# Sheet2.net
KiCad netlist of a schematic drawn in Altium Designer
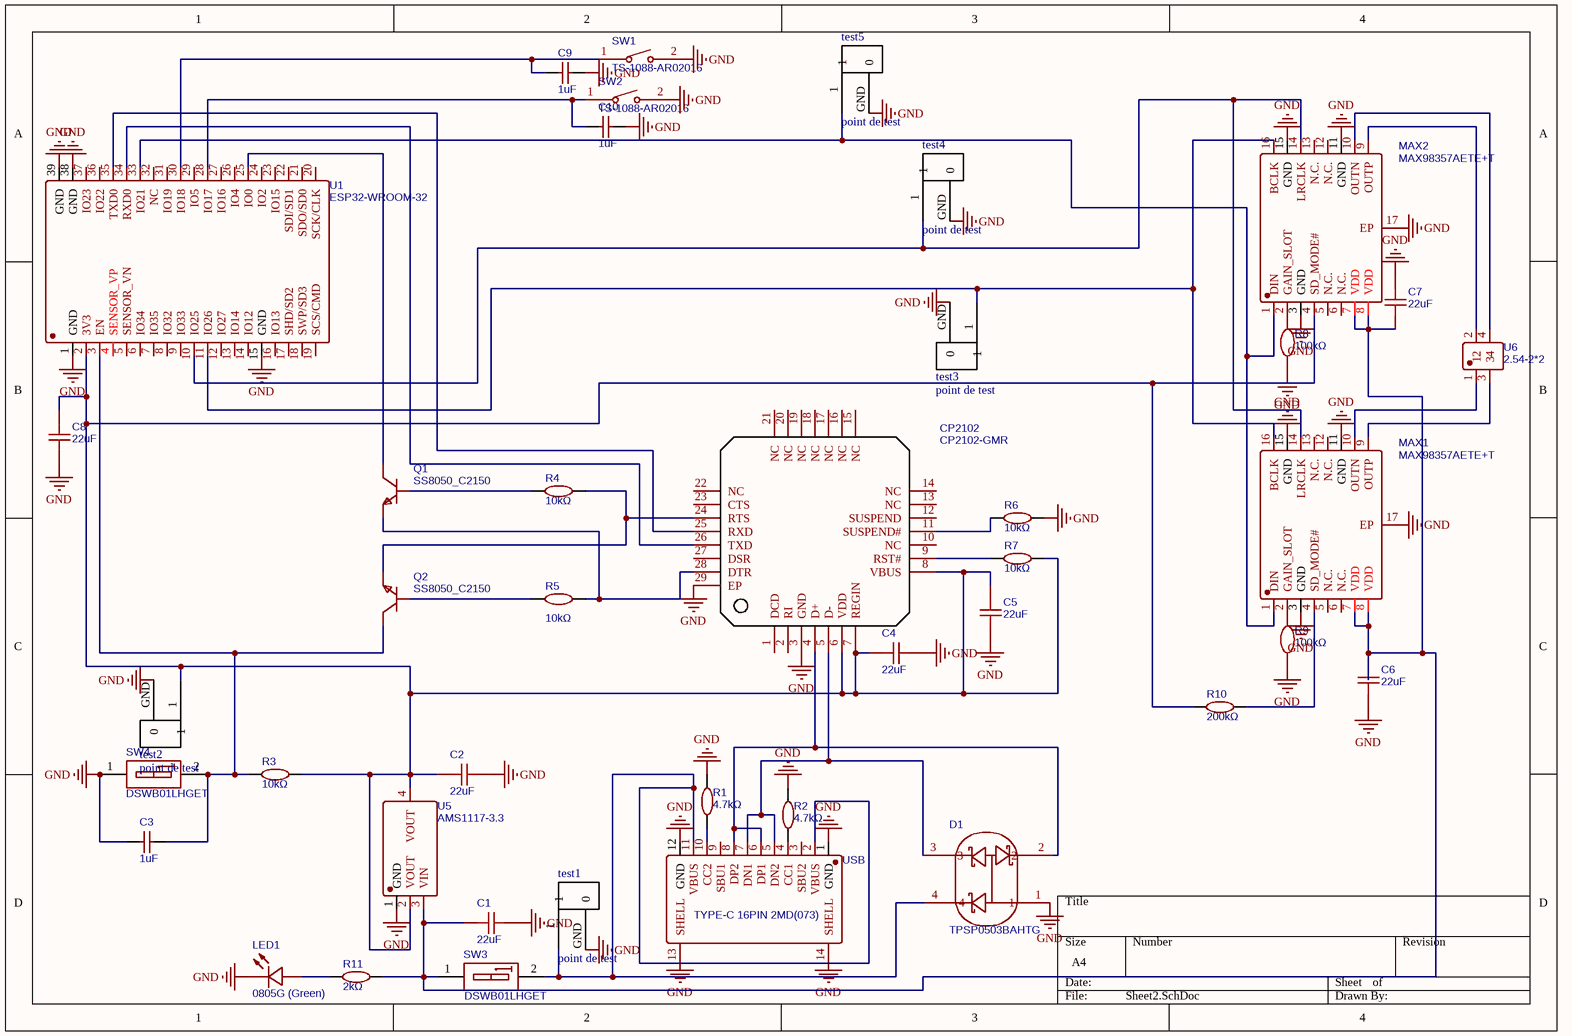
[diagram p0: Sheet2.SchDoc]

(export (version "E")
  (design (tool "Eeschema 10.0.6"))
  (components
    (comp (ref "C1")
      (value "22uF")
      (footprint "C0805")
      (fields
        (field (name "MANUFACTURER") "SAMSUNG(三星)")
        (field (name "MANUFACTURER PART") "CL21A226MAQNNNE")
      )
      (libsource (lib "LIBRAIRIE PROJET") (part "22uF"))
    )
    (comp (ref "C2")
      (value "22uF")
      (footprint "C0805")
      (fields
        (field (name "MANUFACTURER") "SAMSUNG(三星)")
        (field (name "MANUFACTURER PART") "CL21A226MAQNNNE")
      )
      (libsource (lib "LIBRAIRIE PROJET") (part "22uF"))
    )
    (comp (ref "C3")
      (value "1uF")
      (footprint "C0805")
      (fields
        (field (name "MANUFACTURER PART") "CL21B105KBFNNNE")
        (field (name "MANUFACTURER") "SAMSUNG(三星)")
      )
      (libsource (lib "LIBRAIRIE PROJET") (part "1uF"))
    )
    (comp (ref "C4")
      (value "22uF")
      (footprint "C0805")
      (fields
        (field (name "MANUFACTURER") "SAMSUNG(三星)")
        (field (name "MANUFACTURER PART") "CL21A226MAQNNNE")
      )
      (libsource (lib "LIBRAIRIE PROJET") (part "22uF"))
    )
    (comp (ref "C5")
      (value "22uF")
      (footprint "C0805")
      (fields
        (field (name "MANUFACTURER") "SAMSUNG(三星)")
        (field (name "MANUFACTURER PART") "CL21A226MAQNNNE")
      )
      (libsource (lib "LIBRAIRIE PROJET") (part "22uF"))
    )
    (comp (ref "C6")
      (value "22uF")
      (footprint "C0805")
      (fields
        (field (name "MANUFACTURER") "SAMSUNG(三星)")
        (field (name "MANUFACTURER PART") "CL21A226MAQNNNE")
      )
      (libsource (lib "LIBRAIRIE PROJET") (part "22uF"))
    )
    (comp (ref "C7")
      (value "22uF")
      (footprint "C0805")
      (fields
        (field (name "MANUFACTURER") "SAMSUNG(三星)")
        (field (name "MANUFACTURER PART") "CL21A226MAQNNNE")
      )
      (libsource (lib "LIBRAIRIE PROJET") (part "22uF"))
    )
    (comp (ref "C8")
      (value "22uF")
      (footprint "C0805")
      (fields
        (field (name "MANUFACTURER") "SAMSUNG(三星)")
        (field (name "MANUFACTURER PART") "CL21A226MAQNNNE")
      )
      (libsource (lib "LIBRAIRIE PROJET") (part "22uF"))
    )
    (comp (ref "C9")
      (value "1uF")
      (footprint "C0805")
      (fields
        (field (name "MANUFACTURER PART") "CL21B105KBFNNNE")
        (field (name "MANUFACTURER") "SAMSUNG(三星)")
      )
      (libsource (lib "LIBRAIRIE PROJET") (part "1uF"))
    )
    (comp (ref "C10")
      (value "1uF")
      (footprint "C0805")
      (fields
        (field (name "MANUFACTURER PART") "CL21B105KBFNNNE")
        (field (name "MANUFACTURER") "SAMSUNG(三星)")
      )
      (libsource (lib "LIBRAIRIE PROJET") (part "1uF"))
    )
    (comp (ref "CP2102")
      (value "CP2102-GMR")
      (footprint "WQFN-28_L5.0-W5.0-P0.50-BL-EP3.2")
      (fields (field (name "MANUFACTURER") "SKYWORKS/SILICON LABS(芯科)"))
      (libsource (lib "LIBRAIRIE PROJET") (part "CP2102-GMR"))
    )
    (comp (ref "D1")
      (value "TPSP0503BAHTG")
      (footprint "SOT-143-4_L2.9-W1.3-P1.92-LS2.4-BL")
      (fields (field (name "MANUFACTURER") "TECH PUBLIC(台舟)") (field (name "CONTRIBUTOR") "LCSC"))
      (libsource (lib "LIBRAIRIE PROJET") (part "TPSP0503BAHTG"))
    )
    (comp (ref "LED1")
      (value "0805G (Green)")
      (footprint "LED0805-R-RD")
      (fields (field (name "MANUFACTURER") "KENTO") (field (name "MANUFACTURER PART") "KT-0805翠绿"))
      (libsource (lib "LIBRAIRIE PROJET") (part "0805G (Green)"))
    )
    (comp (ref "MAX1")
      (value "MAX98357AETE+T")
      (footprint "TQFN-16_L3.0-W3.0-P0.50-BL-EP1.5")
      (fields (field (name "MANUFACTURER") "ADI(亚德诺)/MAXIM(美信)") (field (name "CONTRIBUTOR") "LCSC"))
      (libsource (lib "LIBRAIRIE PROJET") (part "MAX98357AETE+T"))
    )
    (comp (ref "MAX2")
      (value "MAX98357AETE+T")
      (footprint "TQFN-16_L3.0-W3.0-P0.50-BL-EP1.5")
      (fields (field (name "MANUFACTURER") "ADI(亚德诺)/MAXIM(美信)") (field (name "CONTRIBUTOR") "LCSC"))
      (libsource (lib "LIBRAIRIE PROJET") (part "MAX98357AETE+T"))
    )
    (comp (ref "Q1")
      (value "SS8050_C2150")
      (footprint "SOT-23-3_L2.9-W1.3-P1.90-LS2.4-BR")
      (fields (field (name "MANUFACTURER") "CJ(江苏长电/长晶)") (field (name "MANUFACTURER PART") "SS8050"))
      (libsource (lib "LIBRAIRIE PROJET") (part "SS8050_C2150"))
    )
    (comp (ref "Q2")
      (value "SS8050_C2150")
      (footprint "SOT-23-3_L2.9-W1.3-P1.90-LS2.4-BR")
      (fields (field (name "MANUFACTURER") "CJ(江苏长电/长晶)") (field (name "MANUFACTURER PART") "SS8050"))
      (libsource (lib "LIBRAIRIE PROJET") (part "SS8050_C2150"))
    )
    (comp (ref "R1")
      (value "4.7kΩ")
      (footprint "R0805")
      (fields
        (field (name "MANUFACTURER") "UNI-ROYAL(厚声)")
        (field (name "MANUFACTURER PART") "0805W8F4701T5E")
      )
      (libsource (lib "LIBRAIRIE PROJET") (part "4.7kΩ"))
    )
    (comp (ref "R2")
      (value "4.7kΩ")
      (footprint "R0805")
      (fields
        (field (name "MANUFACTURER") "UNI-ROYAL(厚声)")
        (field (name "MANUFACTURER PART") "0805W8F4701T5E")
      )
      (libsource (lib "LIBRAIRIE PROJET") (part "4.7kΩ"))
    )
    (comp (ref "R3")
      (value "10kΩ")
      (footprint "R0805")
      (fields
        (field (name "MANUFACTURER") "UNI-ROYAL(厚声)")
        (field (name "MANUFACTURER PART") "0805W8F1002T5E")
      )
      (libsource (lib "LIBRAIRIE PROJET") (part "10kΩ"))
    )
    (comp (ref "R4")
      (value "10kΩ")
      (footprint "R0805")
      (fields
        (field (name "MANUFACTURER") "UNI-ROYAL(厚声)")
        (field (name "MANUFACTURER PART") "0805W8F1002T5E")
      )
      (libsource (lib "LIBRAIRIE PROJET") (part "10kΩ"))
    )
    (comp (ref "R5")
      (value "10kΩ")
      (footprint "R0805")
      (fields
        (field (name "MANUFACTURER") "UNI-ROYAL(厚声)")
        (field (name "MANUFACTURER PART") "0805W8F1002T5E")
      )
      (libsource (lib "LIBRAIRIE PROJET") (part "10kΩ"))
    )
    (comp (ref "R6")
      (value "10kΩ")
      (footprint "R0805")
      (fields
        (field (name "MANUFACTURER") "UNI-ROYAL(厚声)")
        (field (name "MANUFACTURER PART") "0805W8F1002T5E")
      )
      (libsource (lib "LIBRAIRIE PROJET") (part "10kΩ"))
    )
    (comp (ref "R7")
      (value "10kΩ")
      (footprint "R0805")
      (fields
        (field (name "MANUFACTURER") "UNI-ROYAL(厚声)")
        (field (name "MANUFACTURER PART") "0805W8F1002T5E")
      )
      (libsource (lib "LIBRAIRIE PROJET") (part "10kΩ"))
    )
    (comp (ref "R8")
      (value "100kΩ")
      (footprint "R0805")
      (fields
        (field (name "MANUFACTURER") "FOJAN(富捷)")
        (field (name "MANUFACTURER PART") "FRC0805J104 TS")
        (field (name "CONTRIBUTOR") "lcsc")
      )
      (libsource (lib "LIBRAIRIE PROJET") (part "100kΩ"))
    )
    (comp (ref "R9")
      (value "100kΩ")
      (footprint "R0805")
      (fields
        (field (name "MANUFACTURER") "FOJAN(富捷)")
        (field (name "MANUFACTURER PART") "FRC0805J104 TS")
        (field (name "CONTRIBUTOR") "lcsc")
      )
      (libsource (lib "LIBRAIRIE PROJET") (part "100kΩ"))
    )
    (comp (ref "R10")
      (value "200kΩ")
      (footprint "R0805")
      (fields
        (field (name "MANUFACTURER") "UNI-ROYAL(厚声)")
        (field (name "MANUFACTURER PART") "0805W8F2003T5E")
      )
      (libsource (lib "LIBRAIRIE PROJET") (part "200kΩ"))
    )
    (comp (ref "R11")
      (value "2kΩ")
      (footprint "R0805")
      (fields
        (field (name "MANUFACTURER") "UNI-ROYAL(厚声)")
        (field (name "MANUFACTURER PART") "0805W8F2001T5E")
      )
      (libsource (lib "LIBRAIRIE PROJET") (part "2kΩ"))
    )
    (comp (ref "SW1")
      (value "TS-1088-AR02016")
      (footprint "SW-SMD_L3.9-W3.0-P4.45")
      (fields (field (name "MANUFACTURER") "XUNPU(讯普)") (field (name "CONTRIBUTOR") "LCSC"))
      (libsource (lib "LIBRAIRIE PROJET") (part "TS-1088-AR02016"))
    )
    (comp (ref "SW2")
      (value "TS-1088-AR02016")
      (footprint "SW-SMD_L3.9-W3.0-P4.45")
      (fields (field (name "MANUFACTURER") "XUNPU(讯普)") (field (name "CONTRIBUTOR") "LCSC"))
      (libsource (lib "LIBRAIRIE PROJET") (part "TS-1088-AR02016"))
    )
    (comp (ref "SW3")
      (value "DSWB01LHGET")
      (footprint "SW-TH_DSWB01LHGET")
      (fields (field (name "MANUFACTURER") "YE"))
      (libsource (lib "LIBRAIRIE PROJET") (part "DSWB01LHGET"))
    )
    (comp (ref "SW4")
      (value "DSWB01LHGET")
      (footprint "SW-TH_DSWB01LHGET")
      (fields (field (name "MANUFACTURER") "YE"))
      (libsource (lib "LIBRAIRIE PROJET") (part "DSWB01LHGET"))
    )
    (comp (ref "test1")
      (value "point de test")
      (footprint "LIBRAIRIE PCB:point de test")
      (libsource (lib "LIBRAIRIE PROJET") (part "point de test"))
    )
    (comp (ref "test2")
      (value "point de test")
      (footprint "LIBRAIRIE PCB:point de test")
      (libsource (lib "LIBRAIRIE PROJET") (part "point de test"))
    )
    (comp (ref "test3")
      (value "point de test")
      (footprint "LIBRAIRIE PCB:point de test")
      (libsource (lib "LIBRAIRIE PROJET") (part "point de test"))
    )
    (comp (ref "test4")
      (value "point de test")
      (footprint "LIBRAIRIE PCB:point de test")
      (libsource (lib "LIBRAIRIE PROJET") (part "point de test"))
    )
    (comp (ref "test5")
      (value "point de test")
      (footprint "LIBRAIRIE PCB:point de test")
      (libsource (lib "LIBRAIRIE PROJET") (part "point de test"))
    )
    (comp (ref "U1")
      (value "ESP32-WROOM-32")
      (footprint "WIFIM-SMD_ESP32-WROOM-32-N4")
      (fields
        (field (name "MANUFACTURER") "ESPRESSIF(乐鑫)")
        (field (name "MANUFACTURER PART") "ESP32-WROOM-32-N4")
        (field (name "CONTRIBUTOR") "LCSC")
      )
      (libsource (lib "LIBRAIRIE PROJET") (part "ESP32-WROOM-32"))
    )
    (comp (ref "U5")
      (value "AMS1117-3.3")
      (footprint "SOT-223-3_L6.5-W3.4-P2.30-LS7.0-BR")
      (fields (field (name "MANUFACTURER") "AMS"))
      (libsource (lib "LIBRAIRIE PROJET") (part "AMS1117-3.3"))
    )
    (comp (ref "U6")
      (value "2.54-2*2")
      (footprint "HDR-TH_4P-P2.54-V-F-R2-C2-S2.54")
      (fields (field (name "MANUFACTURER") "ZHOURI(洲日)") (field (name "CONTRIBUTOR") "LCSC"))
      (libsource (lib "LIBRAIRIE PROJET") (part "2.54-2*2"))
    )
    (comp (ref "USB")
      (value "TYPE-C 16PIN 2MD(073)")
      (footprint "USB-C-SMD_TYPE-C-6PIN-2MD-073")
      (fields (field (name "MANUFACTURER") "SHOU HAN(首韩)") (field (name "CONTRIBUTOR") "LCSC"))
      (libsource (lib "LIBRAIRIE PROJET") (part "TYPE-C 16PIN 2MD(073)"))
    )
  )
  (nets
    (net (code "1") (name "GND") (class "Default")
      (node (ref "C1") (pin "2") (pinfunction "2_2") (pintype "passive"))
      (node (ref "C10") (pin "2") (pinfunction "2_2") (pintype "passive"))
      (node (ref "C2") (pin "2") (pinfunction "2_2") (pintype "passive"))
      (node (ref "C3") (pin "1") (pinfunction "1_1") (pintype "passive"))
      (node (ref "C4") (pin "2") (pinfunction "2_2") (pintype "passive"))
      (node (ref "C5") (pin "1") (pinfunction "1_1") (pintype "passive"))
      (node (ref "C6") (pin "1") (pinfunction "1_1") (pintype "passive"))
      (node (ref "C7") (pin "2") (pinfunction "2_2") (pintype "passive"))
      (node (ref "C8") (pin "2") (pinfunction "2_2") (pintype "passive"))
      (node (ref "C9") (pin "2") (pinfunction "2_2") (pintype "passive"))
      (node (ref "CP2102") (pin "29") (pinfunction "EP_29") (pintype "passive"))
      (node (ref "CP2102") (pin "3") (pinfunction "GND_3") (pintype "passive"))
      (node (ref "D1") (pin "1") (pinfunction "1_1") (pintype "passive"))
      (node (ref "LED1") (pin "2") (pinfunction "K_2") (pintype "passive"))
      (node (ref "MAX1") (pin "11") (pinfunction "GND_11") (pintype "passive"))
      (node (ref "MAX1") (pin "15") (pinfunction "GND_15") (pintype "passive"))
      (node (ref "MAX1") (pin "17") (pinfunction "EP_17") (pintype "passive"))
      (node (ref "MAX1") (pin "3") (pinfunction "GND_3") (pintype "passive"))
      (node (ref "MAX2") (pin "11") (pinfunction "GND_11") (pintype "passive"))
      (node (ref "MAX2") (pin "15") (pinfunction "GND_15") (pintype "passive"))
      (node (ref "MAX2") (pin "17") (pinfunction "EP_17") (pintype "passive"))
      (node (ref "MAX2") (pin "3") (pinfunction "GND_3") (pintype "passive"))
      (node (ref "R1") (pin "2") (pinfunction "2_2") (pintype "passive"))
      (node (ref "R2") (pin "2") (pinfunction "2_2") (pintype "passive"))
      (node (ref "R6") (pin "2") (pinfunction "2_2") (pintype "passive"))
      (node (ref "R8") (pin "1") (pinfunction "1_1") (pintype "passive"))
      (node (ref "R9") (pin "1") (pinfunction "1_1") (pintype "passive"))
      (node (ref "SW1") (pin "2") (pinfunction "2_2") (pintype "passive"))
      (node (ref "SW2") (pin "2") (pinfunction "2_2") (pintype "passive"))
      (node (ref "SW4") (pin "1") (pinfunction "A1_1") (pintype "passive"))
      (node (ref "U1") (pin "1") (pinfunction "GND_1") (pintype "passive"))
      (node (ref "U1") (pin "15") (pinfunction "GND_15") (pintype "passive"))
      (node (ref "U1") (pin "38") (pinfunction "GND_38") (pintype "passive"))
      (node (ref "U1") (pin "39") (pinfunction "GND_39") (pintype "passive"))
      (node (ref "U5") (pin "1") (pinfunction "GND_1") (pintype "passive"))
      (node (ref "USB") (pin "1") (pinfunction "GND_1") (pintype "passive"))
      (node (ref "USB") (pin "12") (pinfunction "GND_12") (pintype "passive"))
      (node (ref "USB") (pin "13") (pinfunction "SHELL_13") (pintype "passive"))
      (node (ref "USB") (pin "14") (pinfunction "SHELL_14") (pintype "passive"))
      (node (ref "test1") (pin "GND") (pinfunction "0_GND") (pintype "passive"))
      (node (ref "test2") (pin "GND") (pinfunction "0_GND") (pintype "passive"))
      (node (ref "test3") (pin "GND") (pinfunction "0_GND") (pintype "passive"))
      (node (ref "test4") (pin "GND") (pinfunction "0_GND") (pintype "passive"))
      (node (ref "test5") (pin "GND") (pinfunction "0_GND") (pintype "passive"))
    )
    (net (code "2") (name "Net-(CP2102-D+)") (class "Default")
      (node (ref "CP2102") (pin "4") (pinfunction "D+_4") (pintype "passive"))
      (node (ref "D1") (pin "2") (pinfunction "2_2") (pintype "passive"))
      (node (ref "USB") (pin "6") (pinfunction "DP1_6") (pintype "passive"))
      (node (ref "USB") (pin "8") (pinfunction "DP2_8") (pintype "passive"))
    )
    (net (code "3") (name "Net-(CP2102-D-)") (class "Default")
      (node (ref "CP2102") (pin "5") (pinfunction "D-_5") (pintype "passive"))
      (node (ref "D1") (pin "3") (pinfunction "3_3") (pintype "passive"))
      (node (ref "USB") (pin "5") (pinfunction "DN2_5") (pintype "passive"))
      (node (ref "USB") (pin "7") (pinfunction "DN1_7") (pintype "passive"))
    )
    (net (code "4") (name "Net-(CP2102-DTR)") (class "Default")
      (node (ref "CP2102") (pin "28") (pinfunction "DTR_28") (pintype "passive"))
      (node (ref "Q1") (pin "2") (pinfunction "E_2") (pintype "passive"))
      (node (ref "R5") (pin "2") (pinfunction "2_2") (pintype "passive"))
    )
    (net (code "5") (name "Net-(CP2102-REGIN)") (class "Default")
      (node (ref "C2") (pin "1") (pinfunction "1_1") (pintype "passive"))
      (node (ref "C4") (pin "1") (pinfunction "1_1") (pintype "passive"))
      (node (ref "C5") (pin "2") (pinfunction "2_2") (pintype "passive"))
      (node (ref "C8") (pin "1") (pinfunction "1_1") (pintype "passive"))
      (node (ref "CP2102") (pin "6") (pinfunction "VDD_6") (pintype "passive"))
      (node (ref "CP2102") (pin "7") (pinfunction "REGIN_7") (pintype "passive"))
      (node (ref "CP2102") (pin "8") (pinfunction "VBUS_8") (pintype "passive"))
      (node (ref "MAX2") (pin "4") (pinfunction "SD_MODE#_4") (pintype "passive"))
      (node (ref "R10") (pin "1") (pinfunction "1_1") (pintype "passive"))
      (node (ref "R3") (pin "2") (pinfunction "2_2") (pintype "passive"))
      (node (ref "R7") (pin "2") (pinfunction "2_2") (pintype "passive"))
      (node (ref "U1") (pin "2") (pinfunction "3V3_2") (pintype "passive"))
      (node (ref "U5") (pin "2") (pinfunction "VOUT_2") (pintype "passive"))
      (node (ref "U5") (pin "4") (pinfunction "VOUT_4") (pintype "passive"))
      (node (ref "test2") (pin "1") (pinfunction "1_1") (pintype "passive"))
    )
    (net (code "6") (name "Net-(CP2102-RST#)") (class "Default")
      (node (ref "CP2102") (pin "9") (pinfunction "RST#_9") (pintype "passive"))
      (node (ref "R7") (pin "1") (pinfunction "1_1") (pintype "passive"))
    )
    (net (code "7") (name "Net-(CP2102-RTS)") (class "Default")
      (node (ref "CP2102") (pin "24") (pinfunction "RTS_24") (pintype "passive"))
      (node (ref "Q2") (pin "2") (pinfunction "E_2") (pintype "passive"))
      (node (ref "R4") (pin "2") (pinfunction "2_2") (pintype "passive"))
    )
    (net (code "8") (name "Net-(CP2102-RXD)") (class "Default")
      (node (ref "CP2102") (pin "25") (pinfunction "RXD_25") (pintype "passive"))
      (node (ref "U1") (pin "35") (pinfunction "TXD0_35") (pintype "passive"))
    )
    (net (code "9") (name "Net-(CP2102-SUSPEND#)") (class "Default")
      (node (ref "CP2102") (pin "11") (pinfunction "SUSPEND#_11") (pintype "passive"))
      (node (ref "R6") (pin "1") (pinfunction "1_1") (pintype "passive"))
    )
    (net (code "10") (name "Net-(CP2102-TXD)") (class "Default")
      (node (ref "CP2102") (pin "26") (pinfunction "TXD_26") (pintype "passive"))
      (node (ref "U1") (pin "34") (pinfunction "RXD0_34") (pintype "passive"))
    )
    (net (code "11") (name "Net-(D1-Pad4)") (class "Default")
      (node (ref "D1") (pin "4") (pinfunction "4_4") (pintype "passive"))
      (node (ref "SW3") (pin "2") (pinfunction "2_2") (pintype "passive"))
      (node (ref "USB") (pin "11") (pinfunction "VBUS_11") (pintype "passive"))
      (node (ref "USB") (pin "2") (pinfunction "VBUS_2") (pintype "passive"))
      (node (ref "test1") (pin "1") (pinfunction "1_1") (pintype "passive"))
    )
    (net (code "12") (name "Net-(LED1-A)") (class "Default")
      (node (ref "LED1") (pin "1") (pinfunction "A_1") (pintype "passive"))
      (node (ref "R11") (pin "1") (pinfunction "1_1") (pintype "passive"))
    )
    (net (code "13") (name "Net-(MAX1-BCLK)") (class "Default")
      (node (ref "MAX1") (pin "16") (pinfunction "BCLK_16") (pintype "passive"))
      (node (ref "MAX2") (pin "16") (pinfunction "BCLK_16") (pintype "passive"))
      (node (ref "U1") (pin "11") (pinfunction "IO26_11") (pintype "passive"))
      (node (ref "test3") (pin "1") (pinfunction "1_1") (pintype "passive"))
    )
    (net (code "14") (name "Net-(MAX1-DIN)") (class "Default")
      (node (ref "MAX1") (pin "1") (pinfunction "DIN_1") (pintype "passive"))
      (node (ref "MAX2") (pin "1") (pinfunction "DIN_1") (pintype "passive"))
      (node (ref "U1") (pin "33") (pinfunction "IO21_33") (pintype "passive"))
      (node (ref "test5") (pin "1") (pinfunction "1_1") (pintype "passive"))
    )
    (net (code "15") (name "Net-(MAX1-GAIN_SLOT)") (class "Default")
      (node (ref "MAX1") (pin "2") (pinfunction "GAIN_SLOT_2") (pintype "passive"))
      (node (ref "R9") (pin "2") (pinfunction "2_2") (pintype "passive"))
    )
    (net (code "16") (name "Net-(MAX1-LRCLK)") (class "Default")
      (node (ref "MAX1") (pin "14") (pinfunction "LRCLK_14") (pintype "passive"))
      (node (ref "MAX2") (pin "14") (pinfunction "LRCLK_14") (pintype "passive"))
      (node (ref "U1") (pin "10") (pinfunction "IO25_10") (pintype "passive"))
      (node (ref "test4") (pin "1") (pinfunction "1_1") (pintype "passive"))
    )
    (net (code "17") (name "Net-(MAX1-OUTN)") (class "Default")
      (node (ref "MAX1") (pin "10") (pinfunction "OUTN_10") (pintype "passive"))
      (node (ref "U6") (pin "1") (pinfunction "1_1") (pintype "passive"))
    )
    (net (code "18") (name "Net-(MAX1-OUTP)") (class "Default")
      (node (ref "MAX1") (pin "9") (pinfunction "OUTP_9") (pintype "passive"))
      (node (ref "U6") (pin "3") (pinfunction "3_3") (pintype "passive"))
    )
    (net (code "19") (name "Net-(MAX1-SD_MODE#)") (class "Default")
      (node (ref "MAX1") (pin "4") (pinfunction "SD_MODE#_4") (pintype "passive"))
      (node (ref "R10") (pin "2") (pinfunction "2_2") (pintype "passive"))
    )
    (net (code "20") (name "Net-(MAX2-GAIN_SLOT)") (class "Default")
      (node (ref "MAX2") (pin "2") (pinfunction "GAIN_SLOT_2") (pintype "passive"))
      (node (ref "R8") (pin "2") (pinfunction "2_2") (pintype "passive"))
    )
    (net (code "21") (name "Net-(MAX2-OUTN)") (class "Default")
      (node (ref "MAX2") (pin "10") (pinfunction "OUTN_10") (pintype "passive"))
      (node (ref "U6") (pin "4") (pinfunction "4_4") (pintype "passive"))
    )
    (net (code "22") (name "Net-(MAX2-OUTP)") (class "Default")
      (node (ref "MAX2") (pin "9") (pinfunction "OUTP_9") (pintype "passive"))
      (node (ref "U6") (pin "2") (pinfunction "2_2") (pintype "passive"))
    )
    (net (code "23") (name "Net-(Q1-B)") (class "Default")
      (node (ref "Q1") (pin "1") (pinfunction "B_1") (pintype "passive"))
      (node (ref "R4") (pin "1") (pinfunction "1_1") (pintype "passive"))
    )
    (net (code "24") (name "Net-(Q1-C)") (class "Default")
      (node (ref "Q1") (pin "3") (pinfunction "C_3") (pintype "passive"))
      (node (ref "U1") (pin "25") (pinfunction "IO0_25") (pintype "passive"))
    )
    (net (code "25") (name "Net-(Q2-B)") (class "Default")
      (node (ref "Q2") (pin "1") (pinfunction "B_1") (pintype "passive"))
      (node (ref "R5") (pin "1") (pinfunction "1_1") (pintype "passive"))
    )
    (net (code "26") (name "Net-(Q2-C)") (class "Default")
      (node (ref "C3") (pin "2") (pinfunction "2_2") (pintype "passive"))
      (node (ref "Q2") (pin "3") (pinfunction "C_3") (pintype "passive"))
      (node (ref "R3") (pin "1") (pinfunction "1_1") (pintype "passive"))
      (node (ref "SW4") (pin "2") (pinfunction "2_2") (pintype "passive"))
      (node (ref "U1") (pin "3") (pinfunction "EN_3") (pintype "passive"))
    )
    (net (code "27") (name "Net-(SW3-A1)") (class "Default")
      (node (ref "C1") (pin "1") (pinfunction "1_1") (pintype "passive"))
      (node (ref "C6") (pin "2") (pinfunction "2_2") (pintype "passive"))
      (node (ref "C7") (pin "1") (pinfunction "1_1") (pintype "passive"))
      (node (ref "MAX1") (pin "7") (pinfunction "VDD_7") (pintype "passive"))
      (node (ref "MAX1") (pin "8") (pinfunction "VDD_8") (pintype "passive"))
      (node (ref "MAX2") (pin "7") (pinfunction "VDD_7") (pintype "passive"))
      (node (ref "MAX2") (pin "8") (pinfunction "VDD_8") (pintype "passive"))
      (node (ref "R11") (pin "2") (pinfunction "2_2") (pintype "passive"))
      (node (ref "SW3") (pin "1") (pinfunction "A1_1") (pintype "passive"))
      (node (ref "U5") (pin "3") (pinfunction "VIN_3") (pintype "passive"))
    )
    (net (code "28") (name "Net-(U1-IO17)") (class "Default")
      (node (ref "C10") (pin "1") (pinfunction "1_1") (pintype "passive"))
      (node (ref "SW2") (pin "1") (pinfunction "1_1") (pintype "passive"))
      (node (ref "U1") (pin "28") (pinfunction "IO17_28") (pintype "passive"))
    )
    (net (code "29") (name "Net-(U1-IO18)") (class "Default")
      (node (ref "C9") (pin "1") (pinfunction "1_1") (pintype "passive"))
      (node (ref "SW1") (pin "1") (pinfunction "1_1") (pintype "passive"))
      (node (ref "U1") (pin "30") (pinfunction "IO18_30") (pintype "passive"))
    )
    (net (code "30") (name "Net-(USB-CC1)") (class "Default")
      (node (ref "R2") (pin "1") (pinfunction "1_1") (pintype "passive"))
      (node (ref "USB") (pin "4") (pinfunction "CC1_4") (pintype "passive"))
    )
    (net (code "31") (name "Net-(USB-CC2)") (class "Default")
      (node (ref "R1") (pin "1") (pinfunction "1_1") (pintype "passive"))
      (node (ref "USB") (pin "10") (pinfunction "CC2_10") (pintype "passive"))
    )
    (net (code "32") (name "unconnected-(CP2102-CTS-Pad23)") (class "Default")
      (node (ref "CP2102") (pin "23") (pinfunction "CTS_23") (pintype "passive"))
    )
    (net (code "33") (name "unconnected-(CP2102-DCD-Pad1)") (class "Default")
      (node (ref "CP2102") (pin "1") (pinfunction "DCD_1") (pintype "passive"))
    )
    (net (code "34") (name "unconnected-(CP2102-DSR-Pad27)") (class "Default")
      (node (ref "CP2102") (pin "27") (pinfunction "DSR_27") (pintype "passive"))
    )
    (net (code "35") (name "unconnected-(CP2102-NC-Pad10)") (class "Default")
      (node (ref "CP2102") (pin "10") (pinfunction "NC_10") (pintype "passive"))
    )
    (net (code "36") (name "unconnected-(CP2102-NC-Pad13)") (class "Default")
      (node (ref "CP2102") (pin "13") (pinfunction "NC_13") (pintype "passive"))
    )
    (net (code "37") (name "unconnected-(CP2102-NC-Pad14)") (class "Default")
      (node (ref "CP2102") (pin "14") (pinfunction "NC_14") (pintype "passive"))
    )
    (net (code "38") (name "unconnected-(CP2102-NC-Pad15)") (class "Default")
      (node (ref "CP2102") (pin "15") (pinfunction "NC_15") (pintype "passive"))
    )
    (net (code "39") (name "unconnected-(CP2102-NC-Pad16)") (class "Default")
      (node (ref "CP2102") (pin "16") (pinfunction "NC_16") (pintype "passive"))
    )
    (net (code "40") (name "unconnected-(CP2102-NC-Pad17)") (class "Default")
      (node (ref "CP2102") (pin "17") (pinfunction "NC_17") (pintype "passive"))
    )
    (net (code "41") (name "unconnected-(CP2102-NC-Pad18)") (class "Default")
      (node (ref "CP2102") (pin "18") (pinfunction "NC_18") (pintype "passive"))
    )
    (net (code "42") (name "unconnected-(CP2102-NC-Pad19)") (class "Default")
      (node (ref "CP2102") (pin "19") (pinfunction "NC_19") (pintype "passive"))
    )
    (net (code "43") (name "unconnected-(CP2102-NC-Pad20)") (class "Default")
      (node (ref "CP2102") (pin "20") (pinfunction "NC_20") (pintype "passive"))
    )
    (net (code "44") (name "unconnected-(CP2102-NC-Pad21)") (class "Default")
      (node (ref "CP2102") (pin "21") (pinfunction "NC_21") (pintype "passive"))
    )
    (net (code "45") (name "unconnected-(CP2102-NC-Pad22)") (class "Default")
      (node (ref "CP2102") (pin "22") (pinfunction "NC_22") (pintype "passive"))
    )
    (net (code "46") (name "unconnected-(CP2102-RI-Pad2)") (class "Default")
      (node (ref "CP2102") (pin "2") (pinfunction "RI_2") (pintype "passive"))
    )
    (net (code "47") (name "unconnected-(CP2102-SUSPEND-Pad12)") (class "Default")
      (node (ref "CP2102") (pin "12") (pinfunction "SUSPEND_12") (pintype "passive"))
    )
    (net (code "48") (name "unconnected-(MAX1-N.C.-Pad5)") (class "Default")
      (node (ref "MAX1") (pin "5") (pinfunction "N.C._5") (pintype "passive"))
    )
    (net (code "49") (name "unconnected-(MAX1-N.C.-Pad6)") (class "Default")
      (node (ref "MAX1") (pin "6") (pinfunction "N.C._6") (pintype "passive"))
    )
    (net (code "50") (name "unconnected-(MAX1-N.C.-Pad12)") (class "Default")
      (node (ref "MAX1") (pin "12") (pinfunction "N.C._12") (pintype "passive"))
    )
    (net (code "51") (name "unconnected-(MAX1-N.C.-Pad13)") (class "Default")
      (node (ref "MAX1") (pin "13") (pinfunction "N.C._13") (pintype "passive"))
    )
    (net (code "52") (name "unconnected-(MAX2-N.C.-Pad5)") (class "Default")
      (node (ref "MAX2") (pin "5") (pinfunction "N.C._5") (pintype "passive"))
    )
    (net (code "53") (name "unconnected-(MAX2-N.C.-Pad6)") (class "Default")
      (node (ref "MAX2") (pin "6") (pinfunction "N.C._6") (pintype "passive"))
    )
    (net (code "54") (name "unconnected-(MAX2-N.C.-Pad12)") (class "Default")
      (node (ref "MAX2") (pin "12") (pinfunction "N.C._12") (pintype "passive"))
    )
    (net (code "55") (name "unconnected-(MAX2-N.C.-Pad13)") (class "Default")
      (node (ref "MAX2") (pin "13") (pinfunction "N.C._13") (pintype "passive"))
    )
    (net (code "56") (name "unconnected-(U1-IO2-Pad24)") (class "Default")
      (node (ref "U1") (pin "24") (pinfunction "IO2_24") (pintype "passive"))
    )
    (net (code "57") (name "unconnected-(U1-IO4-Pad26)") (class "Default")
      (node (ref "U1") (pin "26") (pinfunction "IO4_26") (pintype "passive"))
    )
    (net (code "58") (name "unconnected-(U1-IO5-Pad29)") (class "Default")
      (node (ref "U1") (pin "29") (pinfunction "IO5_29") (pintype "passive"))
    )
    (net (code "59") (name "unconnected-(U1-IO12-Pad14)") (class "Default")
      (node (ref "U1") (pin "14") (pinfunction "IO12_14") (pintype "passive"))
    )
    (net (code "60") (name "unconnected-(U1-IO13-Pad16)") (class "Default")
      (node (ref "U1") (pin "16") (pinfunction "IO13_16") (pintype "passive"))
    )
    (net (code "61") (name "unconnected-(U1-IO14-Pad13)") (class "Default")
      (node (ref "U1") (pin "13") (pinfunction "IO14_13") (pintype "passive"))
    )
    (net (code "62") (name "unconnected-(U1-IO15-Pad23)") (class "Default")
      (node (ref "U1") (pin "23") (pinfunction "IO15_23") (pintype "passive"))
    )
    (net (code "63") (name "unconnected-(U1-IO16-Pad27)") (class "Default")
      (node (ref "U1") (pin "27") (pinfunction "IO16_27") (pintype "passive"))
    )
    (net (code "64") (name "unconnected-(U1-IO19-Pad31)") (class "Default")
      (node (ref "U1") (pin "31") (pinfunction "IO19_31") (pintype "passive"))
    )
    (net (code "65") (name "unconnected-(U1-IO22-Pad36)") (class "Default")
      (node (ref "U1") (pin "36") (pinfunction "IO22_36") (pintype "passive"))
    )
    (net (code "66") (name "unconnected-(U1-IO23-Pad37)") (class "Default")
      (node (ref "U1") (pin "37") (pinfunction "IO23_37") (pintype "passive"))
    )
    (net (code "67") (name "unconnected-(U1-IO27-Pad12)") (class "Default")
      (node (ref "U1") (pin "12") (pinfunction "IO27_12") (pintype "passive"))
    )
    (net (code "68") (name "unconnected-(U1-IO32-Pad8)") (class "Default")
      (node (ref "U1") (pin "8") (pinfunction "IO32_8") (pintype "passive"))
    )
    (net (code "69") (name "unconnected-(U1-IO33-Pad9)") (class "Default")
      (node (ref "U1") (pin "9") (pinfunction "IO33_9") (pintype "passive"))
    )
    (net (code "70") (name "unconnected-(U1-IO34-Pad6)") (class "Default")
      (node (ref "U1") (pin "6") (pinfunction "IO34_6") (pintype "passive"))
    )
    (net (code "71") (name "unconnected-(U1-IO35-Pad7)") (class "Default")
      (node (ref "U1") (pin "7") (pinfunction "IO35_7") (pintype "passive"))
    )
    (net (code "72") (name "unconnected-(U1-NC-Pad32)") (class "Default")
      (node (ref "U1") (pin "32") (pinfunction "NC_32") (pintype "passive"))
    )
    (net (code "73") (name "unconnected-(U1-SCK{slash}CLK-Pad20)") (class "Default")
      (node (ref "U1") (pin "20") (pinfunction "SCK/CLK_20") (pintype "passive"))
    )
    (net (code "74") (name "unconnected-(U1-SCS{slash}CMD-Pad19)") (class "Default")
      (node (ref "U1") (pin "19") (pinfunction "SCS/CMD_19") (pintype "passive"))
    )
    (net (code "75") (name "unconnected-(U1-SDI{slash}SD1-Pad22)") (class "Default")
      (node (ref "U1") (pin "22") (pinfunction "SDI/SD1_22") (pintype "passive"))
    )
    (net (code "76") (name "unconnected-(U1-SDO{slash}SD0-Pad21)") (class "Default")
      (node (ref "U1") (pin "21") (pinfunction "SDO/SD0_21") (pintype "passive"))
    )
    (net (code "77") (name "unconnected-(U1-SENSOR_VN-Pad5)") (class "Default")
      (node (ref "U1") (pin "5") (pinfunction "SENSOR_VN_5") (pintype "passive"))
    )
    (net (code "78") (name "unconnected-(U1-SENSOR_VP-Pad4)") (class "Default")
      (node (ref "U1") (pin "4") (pinfunction "SENSOR_VP_4") (pintype "passive"))
    )
    (net (code "79") (name "unconnected-(U1-SHD{slash}SD2-Pad17)") (class "Default")
      (node (ref "U1") (pin "17") (pinfunction "SHD/SD2_17") (pintype "passive"))
    )
    (net (code "80") (name "unconnected-(U1-SWP{slash}SD3-Pad18)") (class "Default")
      (node (ref "U1") (pin "18") (pinfunction "SWP/SD3_18") (pintype "passive"))
    )
    (net (code "81") (name "unconnected-(USB-SBU1-Pad9)") (class "Default")
      (node (ref "USB") (pin "9") (pinfunction "SBU1_9") (pintype "passive"))
    )
    (net (code "82") (name "unconnected-(USB-SBU2-Pad3)") (class "Default")
      (node (ref "USB") (pin "3") (pinfunction "SBU2_3") (pintype "passive"))
    )
  )
)
